# mte1_redraw.net
KiCad netlist of a schematic drawn in EAGLE
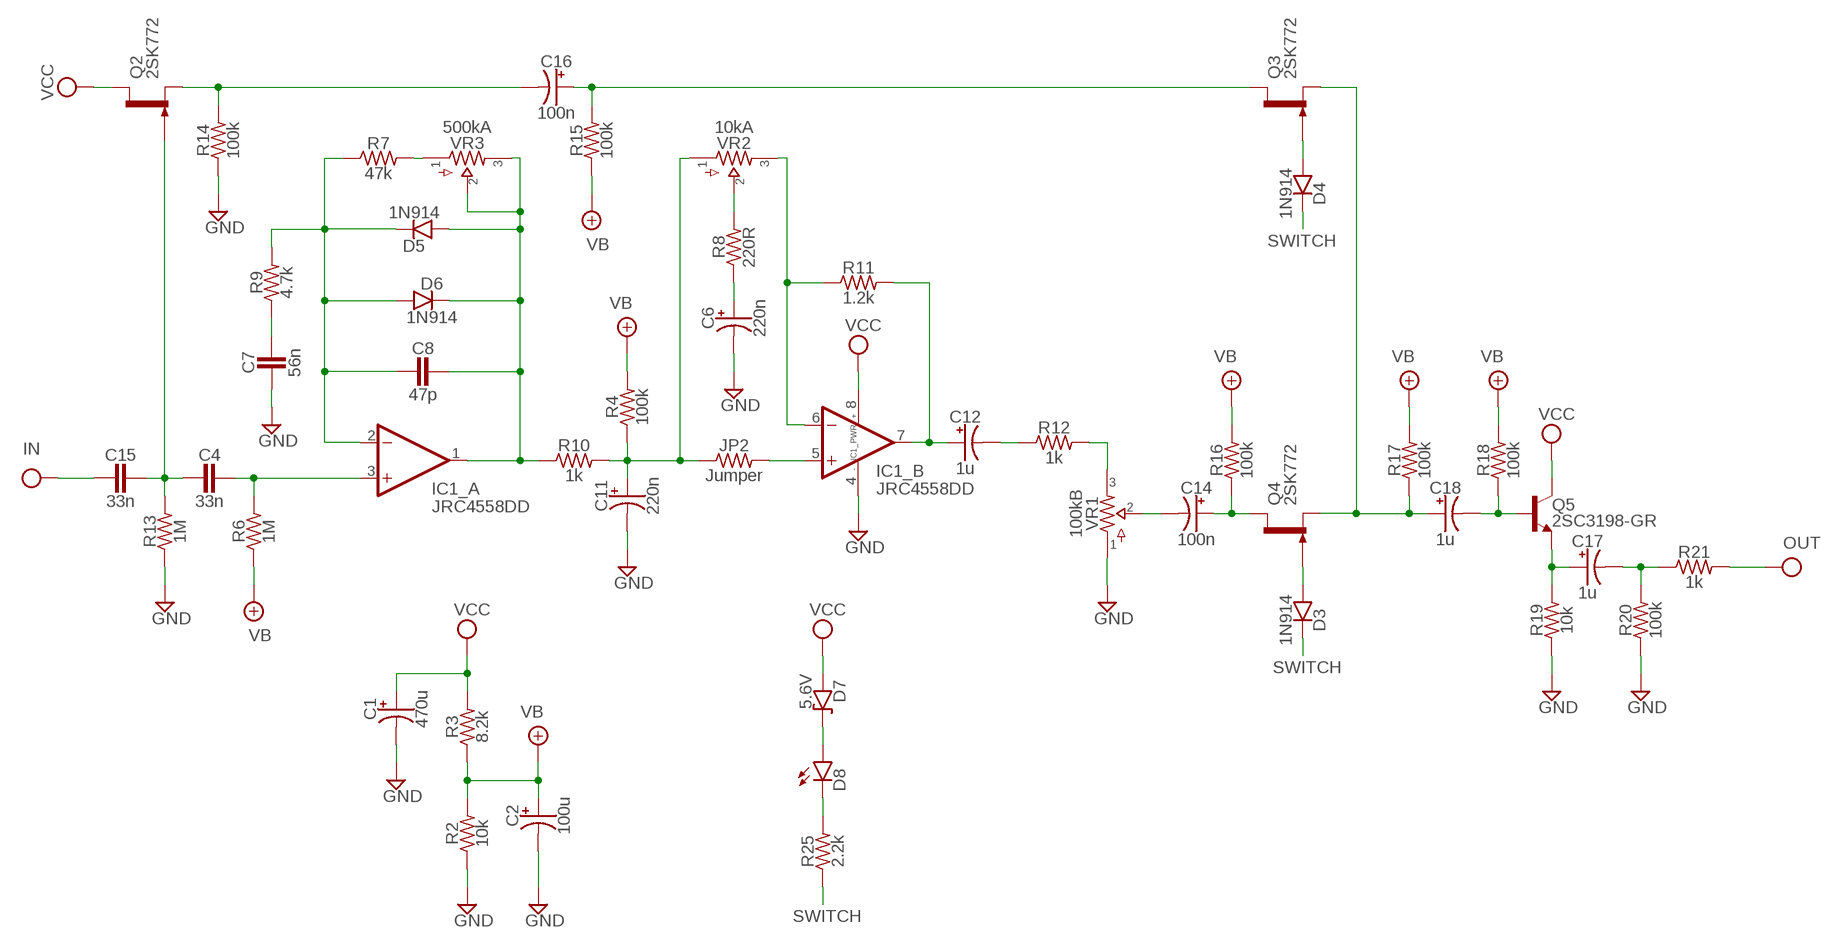
[diagram p0: schematic, sheet 1]

(export (version "E")
  (design (tool "Eeschema 10.0.6"))
  (components
    (comp (ref "C1")
      (value "470u")
      (footprint "eagle-import:040_020")
      (libsource (lib "eagle-import") (part "0400"))
    )
    (comp (ref "C2")
      (value "100u")
      (footprint "eagle-import:040_020")
      (libsource (lib "eagle-import") (part "0400"))
    )
    (comp (ref "C4")
      (value "33n")
      (footprint "eagle-import:BOX_SMALL")
      (libsource (lib "eagle-import") (part "CER/FILMBOX.1"))
    )
    (comp (ref "C6")
      (value "220n")
      (footprint "eagle-import:040_020")
      (libsource (lib "eagle-import") (part "0400"))
    )
    (comp (ref "C7")
      (value "56n")
      (footprint "eagle-import:BOX_SMALL")
      (libsource (lib "eagle-import") (part "CER/FILMBOX.1"))
    )
    (comp (ref "C8")
      (value "47p")
      (footprint "eagle-import:BOX_SMALL")
      (libsource (lib "eagle-import") (part "CER/FILMBOX.1"))
    )
    (comp (ref "C11")
      (value "220n")
      (footprint "eagle-import:040_020")
      (libsource (lib "eagle-import") (part "0400"))
    )
    (comp (ref "C12")
      (value "1u")
      (footprint "eagle-import:040_020")
      (libsource (lib "eagle-import") (part "0400"))
    )
    (comp (ref "C14")
      (value "100n")
      (footprint "eagle-import:040_020")
      (libsource (lib "eagle-import") (part "0400"))
    )
    (comp (ref "C15")
      (value "33n")
      (footprint "eagle-import:BOX_SMALL")
      (libsource (lib "eagle-import") (part "CER/FILMBOX.1"))
    )
    (comp (ref "C16")
      (value "100n")
      (footprint "eagle-import:040_020")
      (libsource (lib "eagle-import") (part "0400"))
    )
    (comp (ref "C17")
      (value "1u")
      (footprint "eagle-import:040_020")
      (libsource (lib "eagle-import") (part "0400"))
    )
    (comp (ref "C18")
      (value "1u")
      (footprint "eagle-import:040_020")
      (libsource (lib "eagle-import") (part "0400"))
    )
    (comp (ref "D3")
      (value "1N914")
      (footprint "eagle-import:DO35-2")
      (libsource (lib "eagle-import") (part "DO35.2"))
    )
    (comp (ref "D4")
      (value "1N914")
      (footprint "eagle-import:DO35-2")
      (libsource (lib "eagle-import") (part "DO35.2"))
    )
    (comp (ref "D5")
      (value "1N914")
      (footprint "eagle-import:DO35-2")
      (libsource (lib "eagle-import") (part "DO35.2"))
    )
    (comp (ref "D6")
      (value "1N914")
      (footprint "eagle-import:DO35-2")
      (libsource (lib "eagle-import") (part "DO35.2"))
    )
    (comp (ref "D7")
      (value "5.6V")
      (footprint "eagle-import:DO41-2")
      (libsource (lib "eagle-import") (part "ZENER.2"))
    )
    (comp (ref "D8")
      (value "LED")
      (footprint "eagle-import:3MM_D")
      (libsource (lib "eagle-import") (part "LED"))
    )
    (comp (ref "IC1")
      (value "JRC4558DD")
      (footprint "eagle-import:DIL0")
      (libsource (lib "eagle-import") (part "DUALTH"))
    )
    (comp (ref "JP2")
      (value "Jumper")
      (footprint "eagle-import:R0207_3")
      (libsource (lib "eagle-import") (part "R_.3B"))
    )
    (comp (ref "Q2")
      (value "2SK772")
      (footprint "eagle-import:TO92-")
      (libsource (lib "eagle-import") (part "2N5457"))
    )
    (comp (ref "Q3")
      (value "2SK772")
      (footprint "eagle-import:TO92-")
      (libsource (lib "eagle-import") (part "2N5457"))
    )
    (comp (ref "Q4")
      (value "2SK772")
      (footprint "eagle-import:TO92-")
      (libsource (lib "eagle-import") (part "2N5457"))
    )
    (comp (ref "Q5")
      (value "2SC3198-GR")
      (footprint "eagle-import:TO92-")
      (libsource (lib "eagle-import") (part "2N3904"))
    )
    (comp (ref "R2")
      (value "10k")
      (footprint "eagle-import:R0207_3")
      (libsource (lib "eagle-import") (part "R_.3B"))
    )
    (comp (ref "R3")
      (value "8.2k")
      (footprint "eagle-import:R0207_3")
      (libsource (lib "eagle-import") (part "R_.3B"))
    )
    (comp (ref "R4")
      (value "100k")
      (footprint "eagle-import:R0207_3")
      (libsource (lib "eagle-import") (part "R_.3B"))
    )
    (comp (ref "R6")
      (value "1M")
      (footprint "eagle-import:R0207_3")
      (libsource (lib "eagle-import") (part "R_.3B"))
    )
    (comp (ref "R7")
      (value "47k")
      (footprint "eagle-import:R0207_3")
      (libsource (lib "eagle-import") (part "R_.3B"))
    )
    (comp (ref "R8")
      (value "220R")
      (footprint "eagle-import:R0207_3")
      (libsource (lib "eagle-import") (part "R_.3B"))
    )
    (comp (ref "R9")
      (value "4.7k")
      (footprint "eagle-import:R0207_3")
      (libsource (lib "eagle-import") (part "R_.3B"))
    )
    (comp (ref "R10")
      (value "1k")
      (footprint "eagle-import:R0207_3")
      (libsource (lib "eagle-import") (part "R_.3B"))
    )
    (comp (ref "R11")
      (value "1.2k")
      (footprint "eagle-import:R0207_3")
      (libsource (lib "eagle-import") (part "R_.3B"))
    )
    (comp (ref "R12")
      (value "1k")
      (footprint "eagle-import:R0207_3")
      (libsource (lib "eagle-import") (part "R_.3B"))
    )
    (comp (ref "R13")
      (value "1M")
      (footprint "eagle-import:R0207_3")
      (libsource (lib "eagle-import") (part "R_.3B"))
    )
    (comp (ref "R14")
      (value "100k")
      (footprint "eagle-import:R0207_3")
      (libsource (lib "eagle-import") (part "R_.3B"))
    )
    (comp (ref "R15")
      (value "100k")
      (footprint "eagle-import:R0207_3")
      (libsource (lib "eagle-import") (part "R_.3B"))
    )
    (comp (ref "R16")
      (value "100k")
      (footprint "eagle-import:R0207_3")
      (libsource (lib "eagle-import") (part "R_.3B"))
    )
    (comp (ref "R17")
      (value "100k")
      (footprint "eagle-import:R0207_3")
      (libsource (lib "eagle-import") (part "R_.3B"))
    )
    (comp (ref "R18")
      (value "100k")
      (footprint "eagle-import:R0207_3")
      (libsource (lib "eagle-import") (part "R_.3B"))
    )
    (comp (ref "R19")
      (value "10k")
      (footprint "eagle-import:R0207_3")
      (libsource (lib "eagle-import") (part "R_.3B"))
    )
    (comp (ref "R20")
      (value "100k")
      (footprint "eagle-import:R0207_3")
      (libsource (lib "eagle-import") (part "R_.3B"))
    )
    (comp (ref "R21")
      (value "1k")
      (footprint "eagle-import:R0207_3")
      (libsource (lib "eagle-import") (part "R_.3B"))
    )
    (comp (ref "R25")
      (value "2.2k")
      (footprint "eagle-import:R0207_3")
      (libsource (lib "eagle-import") (part "R_.3B"))
    )
    (comp (ref "VR1")
      (value "100kB")
      (footprint "eagle-import:16MM")
      (libsource (lib "eagle-import") (part "POTS16MM"))
    )
    (comp (ref "VR2")
      (value "10kA")
      (footprint "eagle-import:16MM")
      (libsource (lib "eagle-import") (part "POTS16MM"))
    )
    (comp (ref "VR3")
      (value "500kA")
      (footprint "eagle-import:16MM")
      (libsource (lib "eagle-import") (part "POTS16MM"))
    )
  )
  (nets
    (net (code "1") (name "/SWITCH") (class "Default")
      (node (ref "D3") (pin "C") (pinfunction "C_C") (pintype "passive"))
      (node (ref "D4") (pin "C") (pinfunction "C_C") (pintype "passive"))
      (node (ref "R25") (pin "1") (pinfunction "1_1") (pintype "passive"))
    )
    (net (code "2") (name "GND") (class "Default")
      (node (ref "C1") (pin "-") (pinfunction "-_-") (pintype "passive"))
      (node (ref "C11") (pin "-") (pinfunction "-_-") (pintype "passive"))
      (node (ref "C2") (pin "-") (pinfunction "-_-") (pintype "passive"))
      (node (ref "C6") (pin "-") (pinfunction "-_-") (pintype "passive"))
      (node (ref "C7") (pin "2") (pinfunction "2_2") (pintype "passive"))
      (node (ref "IC1") (pin "4") (pinfunction "V-_4") (pintype "power_in"))
      (node (ref "R13") (pin "1") (pinfunction "1_1") (pintype "passive"))
      (node (ref "R14") (pin "1") (pinfunction "1_1") (pintype "passive"))
      (node (ref "R19") (pin "1") (pinfunction "1_1") (pintype "passive"))
      (node (ref "R2") (pin "1") (pinfunction "1_1") (pintype "passive"))
      (node (ref "R20") (pin "1") (pinfunction "1_1") (pintype "passive"))
      (node (ref "VR1") (pin "1") (pinfunction "1_1") (pintype "passive"))
    )
    (net (code "3") (name "IN") (class "Default")
      (node (ref "C15") (pin "2") (pinfunction "2_2") (pintype "passive"))
    )
    (net (code "4") (name "Net-(C6-Pad+)") (class "Default")
      (node (ref "C6") (pin "+") (pinfunction "+_+") (pintype "passive"))
      (node (ref "R8") (pin "1") (pinfunction "1_1") (pintype "passive"))
    )
    (net (code "5") (name "Net-(C7-Pad1)") (class "Default")
      (node (ref "C7") (pin "1") (pinfunction "1_1") (pintype "passive"))
      (node (ref "R9") (pin "1") (pinfunction "1_1") (pintype "passive"))
    )
    (net (code "6") (name "Net-(C11-Pad+)") (class "Default")
      (node (ref "C11") (pin "+") (pinfunction "+_+") (pintype "passive"))
      (node (ref "JP2") (pin "1") (pinfunction "1_1") (pintype "passive"))
      (node (ref "R10") (pin "2") (pinfunction "2_2") (pintype "passive"))
      (node (ref "R4") (pin "1") (pinfunction "1_1") (pintype "passive"))
      (node (ref "VR2") (pin "1") (pinfunction "1_1") (pintype "passive"))
    )
    (net (code "7") (name "Net-(C12-Pad-)") (class "Default")
      (node (ref "C12") (pin "-") (pinfunction "-_-") (pintype "passive"))
      (node (ref "R12") (pin "1") (pinfunction "1_1") (pintype "passive"))
    )
    (net (code "8") (name "Net-(C14-Pad-)") (class "Default")
      (node (ref "C14") (pin "-") (pinfunction "-_-") (pintype "passive"))
      (node (ref "VR1") (pin "2") (pinfunction "2_2") (pintype "passive"))
    )
    (net (code "9") (name "Net-(C17-Pad-)") (class "Default")
      (node (ref "C17") (pin "-") (pinfunction "-_-") (pintype "passive"))
      (node (ref "R20") (pin "2") (pinfunction "2_2") (pintype "passive"))
      (node (ref "R21") (pin "1") (pinfunction "1_1") (pintype "passive"))
    )
    (net (code "10") (name "Net-(D8-A)") (class "Default")
      (node (ref "D7") (pin "C") (pinfunction "C_C") (pintype "passive"))
      (node (ref "D8") (pin "ANODE") (pinfunction "A_ANODE") (pintype "passive"))
    )
    (net (code "11") (name "Net-(D8-C)") (class "Default")
      (node (ref "D8") (pin "P$1") (pinfunction "C_P$1") (pintype "passive"))
      (node (ref "R25") (pin "2") (pinfunction "2_2") (pintype "passive"))
    )
    (net (code "12") (name "Net-(IC1A-+IN)") (class "Default")
      (node (ref "C4") (pin "1") (pinfunction "1_1") (pintype "passive"))
      (node (ref "IC1") (pin "3") (pinfunction "+IN_3") (pintype "input"))
      (node (ref "R6") (pin "2") (pinfunction "2_2") (pintype "passive"))
    )
    (net (code "13") (name "Net-(IC1A--IN)") (class "Default")
      (node (ref "C8") (pin "2") (pinfunction "2_2") (pintype "passive"))
      (node (ref "D5") (pin "C") (pinfunction "C_C") (pintype "passive"))
      (node (ref "D6") (pin "A") (pinfunction "A_A") (pintype "passive"))
      (node (ref "IC1") (pin "2") (pinfunction "-IN_2") (pintype "input"))
      (node (ref "R7") (pin "1") (pinfunction "1_1") (pintype "passive"))
      (node (ref "R9") (pin "2") (pinfunction "2_2") (pintype "passive"))
    )
    (net (code "14") (name "Net-(IC1A-OUT)") (class "Default")
      (node (ref "C8") (pin "1") (pinfunction "1_1") (pintype "passive"))
      (node (ref "D5") (pin "A") (pinfunction "A_A") (pintype "passive"))
      (node (ref "D6") (pin "C") (pinfunction "C_C") (pintype "passive"))
      (node (ref "IC1") (pin "1") (pinfunction "OUT_1") (pintype "output"))
      (node (ref "R10") (pin "1") (pinfunction "1_1") (pintype "passive"))
      (node (ref "VR3") (pin "2") (pinfunction "2_2") (pintype "passive"))
      (node (ref "VR3") (pin "3") (pinfunction "3_3") (pintype "passive"))
    )
    (net (code "15") (name "Net-(IC1B-+IN)") (class "Default")
      (node (ref "IC1") (pin "5") (pinfunction "+IN_5") (pintype "input"))
      (node (ref "JP2") (pin "2") (pinfunction "2_2") (pintype "passive"))
    )
    (net (code "16") (name "Net-(IC1B--IN)") (class "Default")
      (node (ref "IC1") (pin "6") (pinfunction "-IN_6") (pintype "input"))
      (node (ref "R11") (pin "1") (pinfunction "1_1") (pintype "passive"))
      (node (ref "VR2") (pin "3") (pinfunction "3_3") (pintype "passive"))
    )
    (net (code "17") (name "Net-(IC1B-OUT)") (class "Default")
      (node (ref "C12") (pin "+") (pinfunction "+_+") (pintype "passive"))
      (node (ref "IC1") (pin "7") (pinfunction "OUT_7") (pintype "output"))
      (node (ref "R11") (pin "2") (pinfunction "2_2") (pintype "passive"))
    )
    (net (code "18") (name "Net-(Q2-G)") (class "Default")
      (node (ref "C15") (pin "1") (pinfunction "1_1") (pintype "passive"))
      (node (ref "C4") (pin "2") (pinfunction "2_2") (pintype "passive"))
      (node (ref "Q2") (pin "1") (pinfunction "G_1") (pintype "passive"))
      (node (ref "R13") (pin "2") (pinfunction "2_2") (pintype "passive"))
    )
    (net (code "19") (name "Net-(Q2-S)") (class "Default")
      (node (ref "C16") (pin "-") (pinfunction "-_-") (pintype "passive"))
      (node (ref "Q2") (pin "2") (pinfunction "S_2") (pintype "passive"))
      (node (ref "R14") (pin "2") (pinfunction "2_2") (pintype "passive"))
    )
    (net (code "20") (name "Net-(Q3-D)") (class "Default")
      (node (ref "C16") (pin "+") (pinfunction "+_+") (pintype "passive"))
      (node (ref "Q3") (pin "3") (pinfunction "D_3") (pintype "passive"))
      (node (ref "R15") (pin "2") (pinfunction "2_2") (pintype "passive"))
    )
    (net (code "21") (name "Net-(Q3-G)") (class "Default")
      (node (ref "D4") (pin "A") (pinfunction "A_A") (pintype "passive"))
      (node (ref "Q3") (pin "1") (pinfunction "G_1") (pintype "passive"))
    )
    (net (code "22") (name "Net-(Q3-S)") (class "Default")
      (node (ref "C18") (pin "+") (pinfunction "+_+") (pintype "passive"))
      (node (ref "Q3") (pin "2") (pinfunction "S_2") (pintype "passive"))
      (node (ref "Q4") (pin "2") (pinfunction "S_2") (pintype "passive"))
      (node (ref "R17") (pin "1") (pinfunction "1_1") (pintype "passive"))
    )
    (net (code "23") (name "Net-(Q4-D)") (class "Default")
      (node (ref "C14") (pin "+") (pinfunction "+_+") (pintype "passive"))
      (node (ref "Q4") (pin "3") (pinfunction "D_3") (pintype "passive"))
      (node (ref "R16") (pin "1") (pinfunction "1_1") (pintype "passive"))
    )
    (net (code "24") (name "Net-(Q4-G)") (class "Default")
      (node (ref "D3") (pin "A") (pinfunction "A_A") (pintype "passive"))
      (node (ref "Q4") (pin "1") (pinfunction "G_1") (pintype "passive"))
    )
    (net (code "25") (name "Net-(Q5-B)") (class "Default")
      (node (ref "C18") (pin "-") (pinfunction "-_-") (pintype "passive"))
      (node (ref "Q5") (pin "2") (pinfunction "B_2") (pintype "passive"))
      (node (ref "R18") (pin "1") (pinfunction "1_1") (pintype "passive"))
    )
    (net (code "26") (name "Net-(Q5-E)") (class "Default")
      (node (ref "C17") (pin "+") (pinfunction "+_+") (pintype "passive"))
      (node (ref "Q5") (pin "3") (pinfunction "E_3") (pintype "passive"))
      (node (ref "R19") (pin "2") (pinfunction "2_2") (pintype "passive"))
    )
    (net (code "27") (name "Net-(R7-Pad2)") (class "Default")
      (node (ref "R7") (pin "2") (pinfunction "2_2") (pintype "passive"))
      (node (ref "VR3") (pin "1") (pinfunction "1_1") (pintype "passive"))
    )
    (net (code "28") (name "Net-(R8-Pad2)") (class "Default")
      (node (ref "R8") (pin "2") (pinfunction "2_2") (pintype "passive"))
      (node (ref "VR2") (pin "2") (pinfunction "2_2") (pintype "passive"))
    )
    (net (code "29") (name "Net-(R12-Pad2)") (class "Default")
      (node (ref "R12") (pin "2") (pinfunction "2_2") (pintype "passive"))
      (node (ref "VR1") (pin "3") (pinfunction "3_3") (pintype "passive"))
    )
    (net (code "30") (name "OUT") (class "Default")
      (node (ref "R21") (pin "2") (pinfunction "2_2") (pintype "passive"))
    )
    (net (code "31") (name "VB") (class "Default")
      (node (ref "C2") (pin "+") (pinfunction "+_+") (pintype "passive"))
      (node (ref "R15") (pin "1") (pinfunction "1_1") (pintype "passive"))
      (node (ref "R16") (pin "2") (pinfunction "2_2") (pintype "passive"))
      (node (ref "R17") (pin "2") (pinfunction "2_2") (pintype "passive"))
      (node (ref "R18") (pin "2") (pinfunction "2_2") (pintype "passive"))
      (node (ref "R2") (pin "2") (pinfunction "2_2") (pintype "passive"))
      (node (ref "R3") (pin "1") (pinfunction "1_1") (pintype "passive"))
      (node (ref "R4") (pin "2") (pinfunction "2_2") (pintype "passive"))
      (node (ref "R6") (pin "1") (pinfunction "1_1") (pintype "passive"))
    )
    (net (code "32") (name "VCC") (class "Default")
      (node (ref "C1") (pin "+") (pinfunction "+_+") (pintype "passive"))
      (node (ref "D7") (pin "A") (pinfunction "A_A") (pintype "passive"))
      (node (ref "IC1") (pin "8") (pinfunction "V+_8") (pintype "power_in"))
      (node (ref "Q2") (pin "3") (pinfunction "D_3") (pintype "passive"))
      (node (ref "Q5") (pin "1") (pinfunction "C_1") (pintype "passive"))
      (node (ref "R3") (pin "2") (pinfunction "2_2") (pintype "passive"))
    )
  )
)
